# ic.net
KiCad netlist of a schematic drawn in Altium Designer
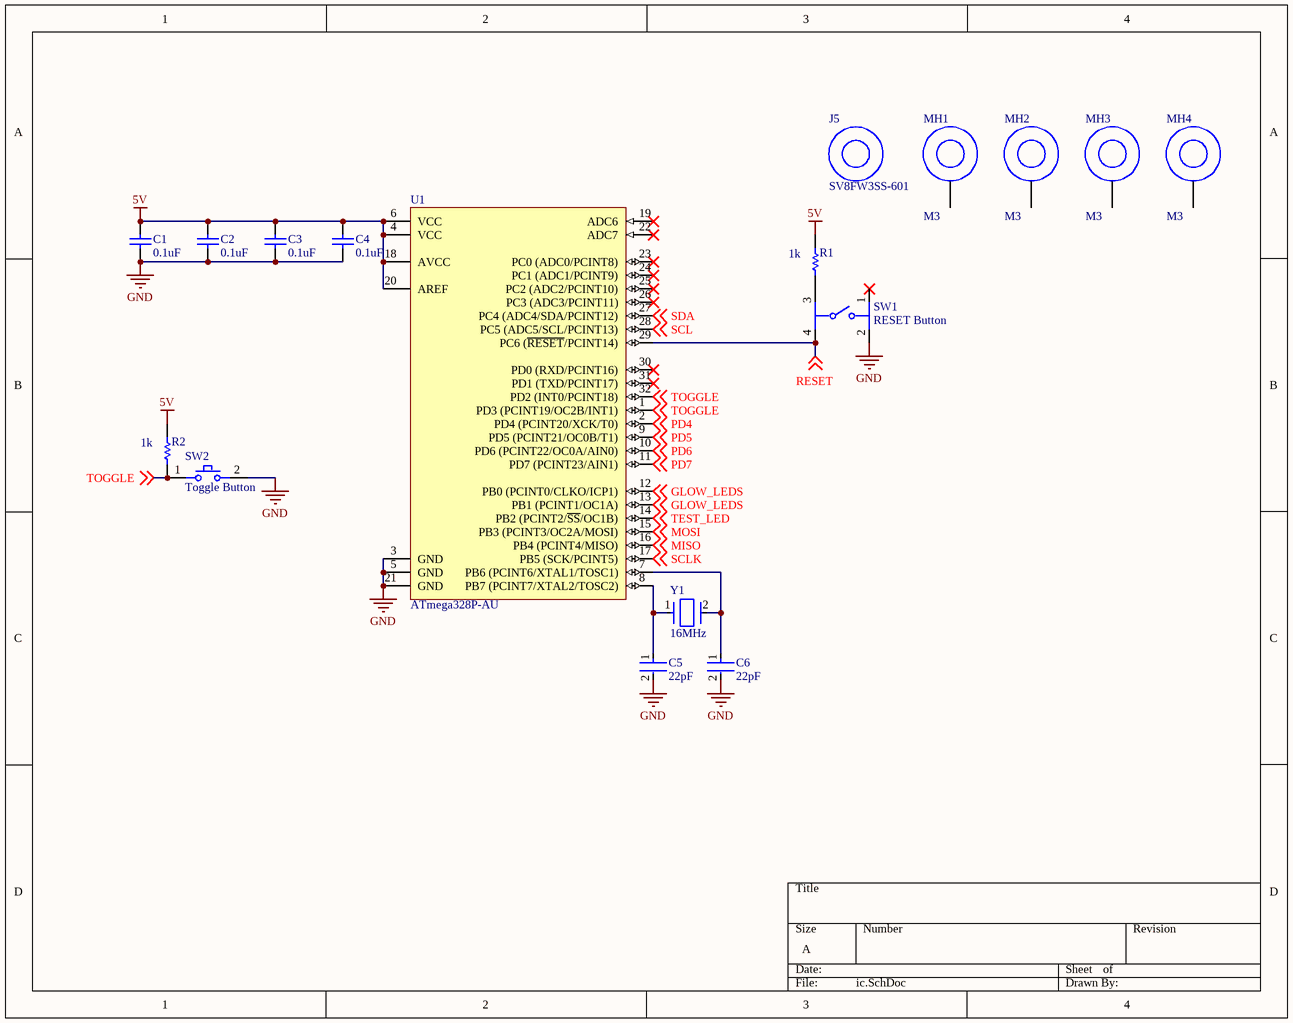
[diagram p0: ic.SchDoc]

(export (version "E")
  (design (tool "Eeschema 10.0.6"))
  (components
    (comp (ref "C1")
      (value "0.1uF")
      (footprint "CAPC2013X135X45ML10T25")
      (description "Chip Capacitor, 0.1 uF, +/- 10%, 50 V, -55 to 125 degC, 0805 (2012 Metric), RoHS, Tape and Reel")
      (fields (field (name "VOLTAGE") "50V") (field (name "TOLERANCE") "10%"))
      (libsource (lib "Altium Content Vault") (part "CAP-NP-2"))
    )
    (comp (ref "C2")
      (value "0.1uF")
      (footprint "CAPC2013X135X45ML10T25")
      (description "Chip Capacitor, 0.1 uF, +/- 10%, 50 V, -55 to 125 degC, 0805 (2012 Metric), RoHS, Tape and Reel")
      (fields (field (name "VOLTAGE") "50V") (field (name "TOLERANCE") "10%"))
      (libsource (lib "Altium Content Vault") (part "CAP-NP-2"))
    )
    (comp (ref "C3")
      (value "0.1uF")
      (footprint "CAPC2013X135X45ML10T25")
      (description "Chip Capacitor, 0.1 uF, +/- 10%, 50 V, -55 to 125 degC, 0805 (2012 Metric), RoHS, Tape and Reel")
      (fields (field (name "VOLTAGE") "50V") (field (name "TOLERANCE") "10%"))
      (libsource (lib "Altium Content Vault") (part "CAP-NP-2"))
    )
    (comp (ref "C4")
      (value "0.1uF")
      (footprint "CAPC2013X135X45ML10T25")
      (description "Chip Capacitor, 0.1 uF, +/- 10%, 50 V, -55 to 125 degC, 0805 (2012 Metric), RoHS, Tape and Reel")
      (fields (field (name "VOLTAGE") "50V") (field (name "TOLERANCE") "10%"))
      (libsource (lib "Altium Content Vault") (part "CAP-NP-2"))
    )
    (comp (ref "C5")
      (value "22pF")
      (footprint "FP-C0805C-DN-MFG")
      (description "CAP CER 22PF 100V 5% NP0 0805")
      (fields
        (field (name "OCTOPART") "https://octopart.com/c0805c220j1gactu-kemet-3791395")
        (field (name "TOLERANCE") "0.05")
      )
      (libsource (lib "Altium Content Vault") (part "b4654b650e69147ec39a6b967a45e02"))
    )
    (comp (ref "C6")
      (value "22pF")
      (footprint "FP-C0805C-DN-MFG")
      (description "CAP CER 22PF 100V 5% NP0 0805")
      (fields
        (field (name "OCTOPART") "https://octopart.com/c0805c220j1gactu-kemet-3791395")
        (field (name "TOLERANCE") "0.05")
      )
      (libsource (lib "Altium Content Vault") (part "b4654b650e69147ec39a6b967a45e02"))
    )
    (comp (ref "J5")
      (value "SV8FW3SS-601")
      (footprint "SV8FW3SS-601")
      (libsource (lib "Fairy Light Sch Lib") (part "SV8FW3SS-601"))
    )
    (comp (ref "MH1")
      (value "M3")
      (footprint "PTH_M3")
      (description "M3 Plated Through Hole")
      (libsource (lib "Schlib1") (part "PTH"))
    )
    (comp (ref "MH2")
      (value "M3")
      (footprint "PTH_M3")
      (description "M3 Plated Through Hole")
      (libsource (lib "Schlib1") (part "PTH"))
    )
    (comp (ref "MH3")
      (value "M3")
      (footprint "PTH_M3")
      (description "M3 Plated Through Hole")
      (libsource (lib "Schlib1") (part "PTH"))
    )
    (comp (ref "MH4")
      (value "M3")
      (footprint "PTH_M3")
      (description "M3 Plated Through Hole")
      (libsource (lib "Schlib1") (part "PTH"))
    )
    (comp (ref "R1")
      (value "1k")
      (footprint "RESC2013X50X30NL20T20")
      (fields (field (name "PART NUMBER") "CRCW08051K00FKEA") (field (name "MANUFACTURER") "Vishay Dale"))
      (libsource (lib "Altium Content Vault") (part "RES"))
    )
    (comp (ref "R2")
      (value "1k")
      (footprint "RESC2013X50X30NL20T20")
      (fields (field (name "PART NUMBER") "CRCW08051K00FKEA") (field (name "MANUFACTURER") "Vishay Dale"))
      (libsource (lib "Altium Content Vault") (part "RES"))
    )
    (comp (ref "SW1")
      (value "RESET Button")
      (footprint "FP-PTS645SM43SMTR92LFS-MFG")
      (description "SWITCH TACTILE SPST-NO 0.05A 12V")
      (fields (field (name "MPN") "PTS645SM43SMTR92LFS"))
      (libsource (lib "Altium Content Vault") (part "1adf0dd01260c80cf25a44bfd6b99ba"))
    )
    (comp (ref "SW2")
      (value "Toggle Button")
      (footprint "FP-B3AL-1003P-MFG")
      (description "SWITCH TACTILE SPST-NO 0.05A 16V")
      (fields (field (name "MPN") "B3AL-1003P"))
      (libsource (lib "Altium Content Vault") (part "69e8347f6a24c021ef43a914a4df441"))
    )
    (comp (ref "U1")
      (value "ATmega328P-AU")
      (footprint "32A_M")
      (libsource (lib "Altium Content Vault") (part "MC-8B-ATM48-SQ32"))
    )
    (comp (ref "Y1")
      (value "16MHz")
      (footprint "FP-XRCHA-MFG")
      (description "CRYSTAL 16.0000MHZ 8PF SMD")
      (fields (field (name "TOLERANCE") "100ppm") (field (name "MPN") "XRCHA16M000F0A01R0"))
      (libsource (lib "Altium Content Vault") (part "c23a69dc6c9e2f18f2079038eb95dd1"))
    )
  )
  (nets
    (net (code "1") (name "5V") (class "Default")
      (node (ref "C1") (pin "2") (pinfunction "2_2") (pintype "passive"))
      (node (ref "C2") (pin "2") (pinfunction "2_2") (pintype "passive"))
      (node (ref "C3") (pin "2") (pinfunction "2_2") (pintype "passive"))
      (node (ref "C4") (pin "2") (pinfunction "2_2") (pintype "passive"))
      (node (ref "R1") (pin "2") (pinfunction "2_2") (pintype "passive"))
      (node (ref "R2") (pin "2") (pinfunction "2_2") (pintype "passive"))
      (node (ref "U1") (pin "18") (pinfunction "AVCC_18") (pintype "power_in"))
      (node (ref "U1") (pin "20") (pinfunction "AREF_20") (pintype "passive"))
      (node (ref "U1") (pin "4") (pinfunction "VCC_4") (pintype "power_in"))
      (node (ref "U1") (pin "6") (pinfunction "VCC_6") (pintype "power_in"))
    )
    (net (code "2") (name "GLOW_LEDS") (class "Default")
      (node (ref "U1") (pin "12") (pinfunction "PB0_(PCINT0/CLKO/ICP1)_12") (pintype "bidirectional"))
      (node (ref "U1") (pin "13") (pinfunction "PB1_(PCINT1/OC1A)_13") (pintype "bidirectional"))
    )
    (net (code "3") (name "GND") (class "Default")
      (node (ref "C1") (pin "1") (pinfunction "1_1") (pintype "passive"))
      (node (ref "C2") (pin "1") (pinfunction "1_1") (pintype "passive"))
      (node (ref "C3") (pin "1") (pinfunction "1_1") (pintype "passive"))
      (node (ref "C4") (pin "1") (pinfunction "1_1") (pintype "passive"))
      (node (ref "C5") (pin "2") (pinfunction "2_2") (pintype "passive"))
      (node (ref "C6") (pin "2") (pinfunction "2_2") (pintype "passive"))
      (node (ref "SW1") (pin "2") (pinfunction "2_2") (pintype "passive"))
      (node (ref "SW2") (pin "2") (pinfunction "2_2") (pintype "passive"))
      (node (ref "U1") (pin "21") (pinfunction "GND_21") (pintype "power_in"))
      (node (ref "U1") (pin "3") (pinfunction "GND_3") (pintype "power_in"))
      (node (ref "U1") (pin "5") (pinfunction "GND_5") (pintype "power_in"))
    )
    (net (code "4") (name "MISO") (class "Default")
      (node (ref "U1") (pin "16") (pinfunction "PB4_(PCINT4/MISO)_16") (pintype "bidirectional"))
    )
    (net (code "5") (name "MOSI") (class "Default")
      (node (ref "U1") (pin "15") (pinfunction "PB3_(PCINT3/OC2A/MOSI)_15") (pintype "bidirectional"))
    )
    (net (code "6") (name "Net-(R1-Pad1)") (class "Default")
      (node (ref "R1") (pin "1") (pinfunction "1_1") (pintype "passive"))
      (node (ref "SW1") (pin "3") (pinfunction "3_3") (pintype "passive"))
    )
    (net (code "7") (name "Net-(U1-PB6_(PCINT6{slash}XTAL1{slash}TOSC1))") (class "Default")
      (node (ref "C6") (pin "1") (pinfunction "1_1") (pintype "passive"))
      (node (ref "U1") (pin "7") (pinfunction "PB6_(PCINT6/XTAL1/TOSC1)_7") (pintype "bidirectional"))
      (node (ref "Y1") (pin "2") (pinfunction "2_2") (pintype "passive"))
    )
    (net (code "8") (name "Net-(U1-PB7_(PCINT7{slash}XTAL2{slash}TOSC2))") (class "Default")
      (node (ref "C5") (pin "1") (pinfunction "1_1") (pintype "passive"))
      (node (ref "U1") (pin "8") (pinfunction "PB7_(PCINT7/XTAL2/TOSC2)_8") (pintype "bidirectional"))
      (node (ref "Y1") (pin "1") (pinfunction "1_1") (pintype "passive"))
    )
    (net (code "9") (name "PD4") (class "Default")
      (node (ref "U1") (pin "2") (pinfunction "PD4_(PCINT20/XCK/T0)_2") (pintype "bidirectional"))
    )
    (net (code "10") (name "PD5") (class "Default")
      (node (ref "U1") (pin "9") (pinfunction "PD5_(PCINT21/OC0B/T1)_9") (pintype "bidirectional"))
    )
    (net (code "11") (name "PD6") (class "Default")
      (node (ref "U1") (pin "10") (pinfunction "PD6_(PCINT22/OC0A/AIN0)_10") (pintype "bidirectional"))
    )
    (net (code "12") (name "PD7") (class "Default")
      (node (ref "U1") (pin "11") (pinfunction "PD7_(PCINT23/AIN1)_11") (pintype "bidirectional"))
    )
    (net (code "13") (name "RESET") (class "Default")
      (node (ref "SW1") (pin "4") (pinfunction "4_4") (pintype "passive"))
      (node (ref "U1") (pin "29") (pinfunction "PC6_(~{RESET}/PCINT14)_29") (pintype "bidirectional"))
    )
    (net (code "14") (name "SCL") (class "Default")
      (node (ref "U1") (pin "28") (pinfunction "PC5_(ADC5/SCL/PCINT13)_28") (pintype "bidirectional"))
    )
    (net (code "15") (name "SCLK") (class "Default")
      (node (ref "U1") (pin "17") (pinfunction "PB5_(SCK/PCINT5)_17") (pintype "bidirectional"))
    )
    (net (code "16") (name "SDA") (class "Default")
      (node (ref "U1") (pin "27") (pinfunction "PC4_(ADC4/SDA/PCINT12)_27") (pintype "bidirectional"))
    )
    (net (code "17") (name "TEST_LED") (class "Default")
      (node (ref "U1") (pin "14") (pinfunction "PB2_(PCINT2/~{SS}/OC1B)_14") (pintype "bidirectional"))
    )
    (net (code "18") (name "TOGGLE") (class "Default")
      (node (ref "R2") (pin "1") (pinfunction "1_1") (pintype "passive"))
      (node (ref "SW2") (pin "1") (pinfunction "1_1") (pintype "passive"))
      (node (ref "U1") (pin "1") (pinfunction "PD3_(PCINT19/OC2B/INT1)_1") (pintype "bidirectional"))
      (node (ref "U1") (pin "32") (pinfunction "PD2_(INT0/PCINT18)_32") (pintype "bidirectional"))
    )
    (net (code "19") (name "unconnected-(MH1-Pad1)") (class "Default")
      (node (ref "MH1") (pin "1") (pinfunction "1_1") (pintype "passive"))
    )
    (net (code "20") (name "unconnected-(MH2-Pad1)") (class "Default")
      (node (ref "MH2") (pin "1") (pinfunction "1_1") (pintype "passive"))
    )
    (net (code "21") (name "unconnected-(MH3-Pad1)") (class "Default")
      (node (ref "MH3") (pin "1") (pinfunction "1_1") (pintype "passive"))
    )
    (net (code "22") (name "unconnected-(MH4-Pad1)") (class "Default")
      (node (ref "MH4") (pin "1") (pinfunction "1_1") (pintype "passive"))
    )
    (net (code "23") (name "unconnected-(SW1-Pad1)") (class "Default")
      (node (ref "SW1") (pin "1") (pinfunction "1_1") (pintype "passive+no_connect"))
    )
    (net (code "24") (name "unconnected-(U1-ADC6-Pad19)") (class "Default")
      (node (ref "U1") (pin "19") (pinfunction "ADC6_19") (pintype "input+no_connect"))
    )
    (net (code "25") (name "unconnected-(U1-ADC7-Pad22)") (class "Default")
      (node (ref "U1") (pin "22") (pinfunction "ADC7_22") (pintype "input+no_connect"))
    )
    (net (code "26") (name "unconnected-(U1-PC0_(ADC0{slash}PCINT8)-Pad23)") (class "Default")
      (node (ref "U1") (pin "23") (pinfunction "PC0_(ADC0/PCINT8)_23") (pintype "bidirectional+no_connect"))
    )
    (net (code "27") (name "unconnected-(U1-PC1_(ADC1{slash}PCINT9)-Pad24)") (class "Default")
      (node (ref "U1") (pin "24") (pinfunction "PC1_(ADC1/PCINT9)_24") (pintype "bidirectional+no_connect"))
    )
    (net (code "28") (name "unconnected-(U1-PC2_(ADC2{slash}PCINT10)-Pad25)") (class "Default")
      (node (ref "U1") (pin "25") (pinfunction "PC2_(ADC2/PCINT10)_25") (pintype "bidirectional+no_connect"))
    )
    (net (code "29") (name "unconnected-(U1-PC3_(ADC3{slash}PCINT11)-Pad26)") (class "Default")
      (node (ref "U1") (pin "26") (pinfunction "PC3_(ADC3/PCINT11)_26") (pintype "bidirectional+no_connect"))
    )
    (net (code "30") (name "unconnected-(U1-PD0_(RXD{slash}PCINT16)-Pad30)") (class "Default")
      (node (ref "U1") (pin "30") (pinfunction "PD0_(RXD/PCINT16)_30") (pintype "bidirectional+no_connect"))
    )
    (net (code "31") (name "unconnected-(U1-PD1_(TXD{slash}PCINT17)-Pad31)") (class "Default")
      (node (ref "U1") (pin "31") (pinfunction "PD1_(TXD/PCINT17)_31") (pintype "bidirectional+no_connect"))
    )
  )
)
